# Brain_0_1_rv1.net
KiCad netlist of a schematic drawn in EAGLE
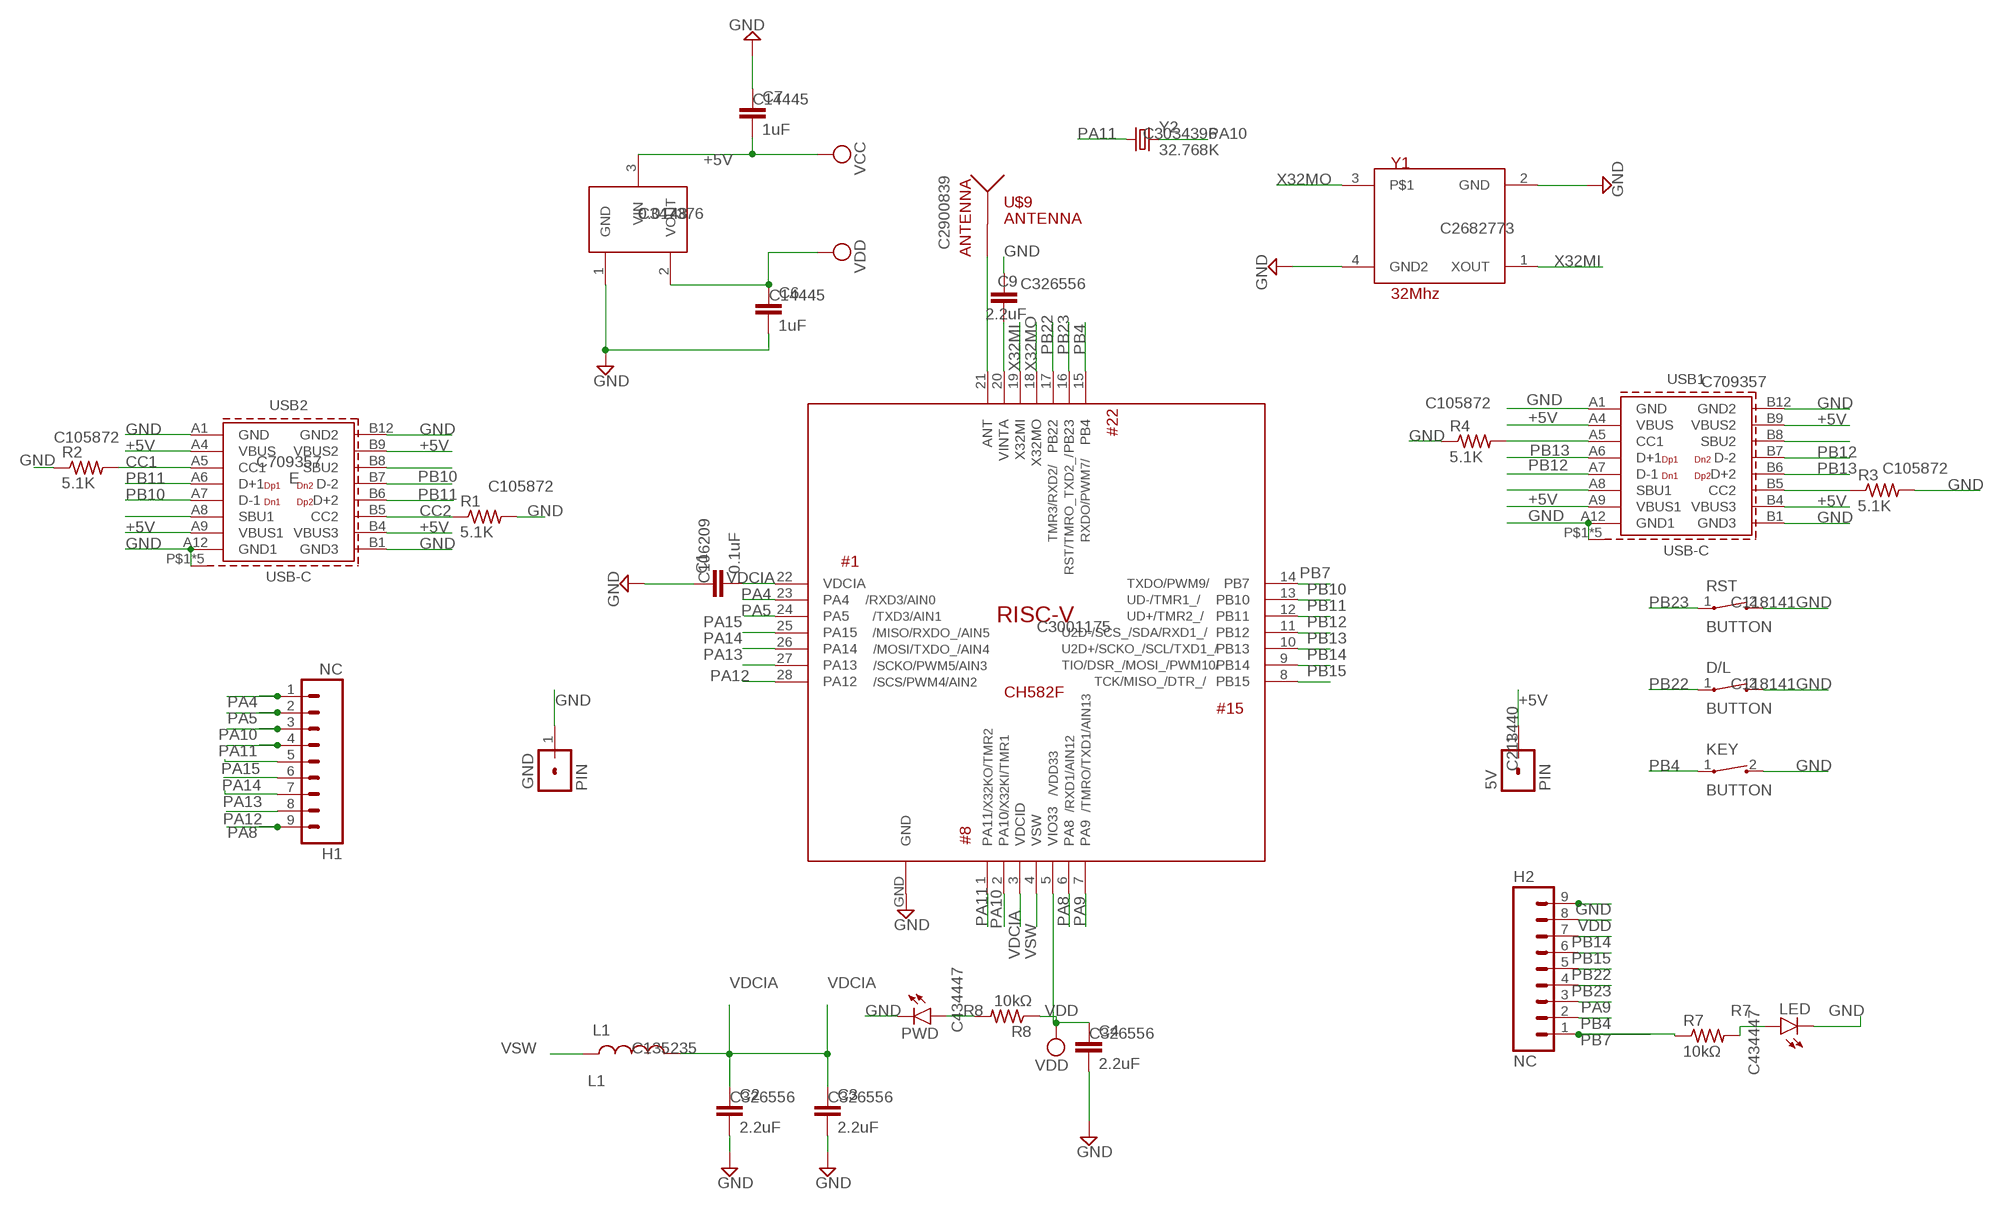
[diagram p0: schematic, sheet 1]

(export (version "E")
  (design (tool "Eeschema 10.0.6"))
  (components
    (comp (ref "5V")
      (value "PIN")
      (footprint "eagle-import:1X01")
      (fields (field (name "LCSC") "C213440"))
      (libsource (lib "eagle-import") (part "PIN"))
    )
    (comp (ref "C1")
      (value "0.1uF")
      (footprint "eagle-import:C1")
      (fields (field (name "LCSC") "C106209"))
      (libsource (lib "eagle-import") (part "C"))
    )
    (comp (ref "C2")
      (value "2.2uF")
      (footprint "eagle-import:C1")
      (fields (field (name "LCSC") "C326556"))
      (libsource (lib "eagle-import") (part "C"))
    )
    (comp (ref "C3")
      (value "2.2uF")
      (footprint "eagle-import:C1")
      (fields (field (name "LCSC") "C326556"))
      (libsource (lib "eagle-import") (part "C"))
    )
    (comp (ref "C4")
      (value "2.2uF")
      (footprint "eagle-import:C1")
      (fields (field (name "LCSC") "C326556"))
      (libsource (lib "eagle-import") (part "C"))
    )
    (comp (ref "C6")
      (value "1uF")
      (footprint "eagle-import:C1")
      (fields (field (name "LCSC") "C14445"))
      (libsource (lib "eagle-import") (part "C"))
    )
    (comp (ref "C7")
      (value "1uF")
      (footprint "eagle-import:C1")
      (fields (field (name "LCSC") "C14445"))
      (libsource (lib "eagle-import") (part "C"))
    )
    (comp (ref "C9")
      (value "2.2uF")
      (footprint "eagle-import:C1")
      (fields (field (name "LCSC") "C326556"))
      (libsource (lib "eagle-import") (part "C"))
    )
    (comp (ref "D/L")
      (value "BUTTON")
      (footprint "eagle-import:SOD8037X250N")
      (fields (field (name "LCSC") "C118141"))
      (libsource (lib "eagle-import") (part "BUTTON"))
    )
    (comp (ref "GND")
      (value "PIN")
      (footprint "eagle-import:1X01")
      (libsource (lib "eagle-import") (part "PIN"))
    )
    (comp (ref "H1")
      (value "NC")
      (footprint "eagle-import:61300911821")
      (libsource (lib "eagle-import") (part "H"))
    )
    (comp (ref "H2")
      (value "NC")
      (footprint "eagle-import:61300911821")
      (libsource (lib "eagle-import") (part "H"))
    )
    (comp (ref "KEY")
      (value "BUTTON")
      (footprint "eagle-import:SOD8037X250N")
      (libsource (lib "eagle-import") (part "BUTTON"))
    )
    (comp (ref "L1")
      (value "L1")
      (footprint "eagle-import:RESC3025X120N")
      (fields (field (name "LCSC") "C135235"))
      (libsource (lib "eagle-import") (part "L1"))
    )
    (comp (ref "LED")
      (value "LED")
      (footprint "eagle-import:CAPCP1005X40N")
      (fields (field (name "LCSC") "C434447"))
      (libsource (lib "eagle-import") (part "LED"))
    )
    (comp (ref "PWD")
      (value "LED")
      (footprint "eagle-import:CAPCP1005X40N")
      (fields (field (name "LCSC") "C434447"))
      (libsource (lib "eagle-import") (part "LED"))
    )
    (comp (ref "R1")
      (value "5.1K")
      (footprint "eagle-import:R0402")
      (fields (field (name "LCSC") "C105872"))
      (libsource (lib "eagle-import") (part "RR0402"))
    )
    (comp (ref "R2")
      (value "5.1K")
      (footprint "eagle-import:R0402")
      (fields (field (name "LCSC") "C105872"))
      (libsource (lib "eagle-import") (part "RR0402"))
    )
    (comp (ref "R3")
      (value "5.1K")
      (footprint "eagle-import:R0402")
      (fields (field (name "LCSC") "C105872"))
      (libsource (lib "eagle-import") (part "RR0402"))
    )
    (comp (ref "R4")
      (value "5.1K")
      (footprint "eagle-import:R0402")
      (fields (field (name "LCSC") "C105872"))
      (libsource (lib "eagle-import") (part "RR0402"))
    )
    (comp (ref "R7")
      (value "10kΩ")
      (footprint "eagle-import:R0402")
      (libsource (lib "eagle-import") (part "RR0402"))
    )
    (comp (ref "R8")
      (value "10kΩ")
      (footprint "eagle-import:R0402")
      (fields (field (name "LCSC_PART") "C25744"))
      (libsource (lib "eagle-import") (part "RR0402"))
    )
    (comp (ref "RST")
      (value "BUTTON")
      (footprint "eagle-import:SOD8037X250N")
      (fields (field (name "LCSC") "C118141"))
      (libsource (lib "eagle-import") (part "BUTTON"))
    )
    (comp (ref "U$8")
      (value "RISC-V")
      (footprint "eagle-import:QFN40P400X400X75-29T280N")
      (fields (field (name "LCSC") "C3001175"))
      (libsource (lib "eagle-import") (part "RISC-V"))
    )
    (comp (ref "U$9")
      (value "ANTENNA")
      (footprint "eagle-import:CAPCP3015X50N")
      (fields (field (name "LCSC") "C2900839"))
      (libsource (lib "eagle-import") (part "ANTENNA"))
    )
    (comp (ref "U1")
      (value "U1")
      (footprint "eagle-import:SOT95P240X90-3N")
      (fields (field (name "LCSC") "C347376") (field (name "PRICE-1000") "0.0148"))
      (libsource (lib "eagle-import") (part "U1"))
    )
    (comp (ref "USB1")
      (value "629722000214")
      (footprint "eagle-import:629722000214")
      (fields (field (name "LCSC") "C709357"))
      (libsource (lib "eagle-import") (part "J1"))
    )
    (comp (ref "USB2")
      (value "629722000214")
      (footprint "eagle-import:629722000214")
      (fields (field (name "LCSC") "C709357"))
      (libsource (lib "eagle-import") (part "J1"))
    )
    (comp (ref "Y1")
      (value "Y1YSX211SL")
      (footprint "eagle-import:OSCCC200X160X50N")
      (fields (field (name "LCSC") "C2682773"))
      (libsource (lib "eagle-import") (part "Y1YSX211SL"))
    )
    (comp (ref "Y2")
      (value "32.768K")
      (footprint "eagle-import:XTAL700X315X230N")
      (fields (field (name "LCSC") "C3034396"))
      (libsource (lib "eagle-import") (part "Y2"))
    )
  )
  (nets
    (net (code "1") (name "/CC1") (class "Default")
      (node (ref "R2") (pin "2") (pinfunction "2_2") (pintype "passive"))
      (node (ref "USB2") (pin "A5") (pinfunction "CC1_A5") (pintype "passive"))
    )
    (net (code "2") (name "/CC2") (class "Default")
      (node (ref "R1") (pin "1") (pinfunction "1_1") (pintype "passive"))
      (node (ref "USB2") (pin "B5") (pinfunction "CC2_B5") (pintype "passive"))
    )
    (net (code "3") (name "/PA4") (class "Default")
      (node (ref "H1") (pin "1") (pinfunction "1_1") (pintype "passive"))
      (node (ref "U$8") (pin "23") (pinfunction "PA4_23") (pintype "bidirectional"))
    )
    (net (code "4") (name "/PA5") (class "Default")
      (node (ref "H1") (pin "2") (pinfunction "2_2") (pintype "passive"))
      (node (ref "U$8") (pin "24") (pinfunction "PA5_24") (pintype "bidirectional"))
    )
    (net (code "5") (name "/PA8") (class "Default")
      (node (ref "H1") (pin "9") (pinfunction "9_9") (pintype "passive"))
      (node (ref "U$8") (pin "6") (pinfunction "PA8_6") (pintype "bidirectional"))
    )
    (net (code "6") (name "/PA9") (class "Default")
      (node (ref "H2") (pin "3") (pinfunction "3_3") (pintype "passive"))
      (node (ref "U$8") (pin "7") (pinfunction "PA9_7") (pintype "bidirectional"))
    )
    (net (code "7") (name "/PA10") (class "Default")
      (node (ref "H1") (pin "3") (pinfunction "3_3") (pintype "passive"))
      (node (ref "U$8") (pin "2") (pinfunction "PA10_2") (pintype "bidirectional"))
      (node (ref "Y2") (pin "2") (pinfunction "2_2") (pintype "passive"))
    )
    (net (code "8") (name "/PA11") (class "Default")
      (node (ref "H1") (pin "4") (pinfunction "4_4") (pintype "passive"))
      (node (ref "U$8") (pin "1") (pinfunction "PA11_1") (pintype "bidirectional"))
      (node (ref "Y2") (pin "1") (pinfunction "1_1") (pintype "passive"))
    )
    (net (code "9") (name "/PA12") (class "Default")
      (node (ref "H1") (pin "8") (pinfunction "8_8") (pintype "passive"))
      (node (ref "U$8") (pin "28") (pinfunction "PA12_28") (pintype "bidirectional"))
    )
    (net (code "10") (name "/PA13") (class "Default")
      (node (ref "H1") (pin "7") (pinfunction "7_7") (pintype "passive"))
      (node (ref "U$8") (pin "27") (pinfunction "PA13_27") (pintype "bidirectional"))
    )
    (net (code "11") (name "/PA14") (class "Default")
      (node (ref "H1") (pin "6") (pinfunction "6_6") (pintype "passive"))
      (node (ref "U$8") (pin "26") (pinfunction "PA14_26") (pintype "bidirectional"))
    )
    (net (code "12") (name "/PA15") (class "Default")
      (node (ref "H1") (pin "5") (pinfunction "5_5") (pintype "passive"))
      (node (ref "U$8") (pin "25") (pinfunction "PA15_25") (pintype "bidirectional"))
    )
    (net (code "13") (name "/PB4") (class "Default")
      (node (ref "H2") (pin "2") (pinfunction "2_2") (pintype "passive"))
      (node (ref "KEY") (pin "1") (pinfunction "1_1") (pintype "passive"))
      (node (ref "U$8") (pin "15") (pinfunction "PB4_15") (pintype "bidirectional"))
    )
    (net (code "14") (name "/PB7") (class "Default")
      (node (ref "H2") (pin "1") (pinfunction "1_1") (pintype "passive"))
      (node (ref "R7") (pin "1") (pinfunction "1_1") (pintype "passive"))
      (node (ref "U$8") (pin "14") (pinfunction "PB7_14") (pintype "bidirectional"))
    )
    (net (code "15") (name "/PB10") (class "Default")
      (node (ref "U$8") (pin "13") (pinfunction "PB10_13") (pintype "bidirectional"))
      (node (ref "USB2") (pin "A7") (pinfunction "D-1_A7") (pintype "passive"))
      (node (ref "USB2") (pin "B7") (pinfunction "D-2_B7") (pintype "passive"))
    )
    (net (code "16") (name "/PB11") (class "Default")
      (node (ref "U$8") (pin "12") (pinfunction "PB11_12") (pintype "bidirectional"))
      (node (ref "USB2") (pin "A6") (pinfunction "D+1_A6") (pintype "passive"))
      (node (ref "USB2") (pin "B6") (pinfunction "D+2_B6") (pintype "passive"))
    )
    (net (code "17") (name "/PB12") (class "Default")
      (node (ref "U$8") (pin "11") (pinfunction "PB12_11") (pintype "bidirectional"))
      (node (ref "USB1") (pin "A7") (pinfunction "D-1_A7") (pintype "passive"))
      (node (ref "USB1") (pin "B7") (pinfunction "D-2_B7") (pintype "passive"))
    )
    (net (code "18") (name "/PB13") (class "Default")
      (node (ref "U$8") (pin "10") (pinfunction "PB13_10") (pintype "bidirectional"))
      (node (ref "USB1") (pin "A6") (pinfunction "D+1_A6") (pintype "passive"))
      (node (ref "USB1") (pin "B6") (pinfunction "D+2_B6") (pintype "passive"))
    )
    (net (code "19") (name "/PB14") (class "Default")
      (node (ref "H2") (pin "7") (pinfunction "7_7") (pintype "passive"))
      (node (ref "U$8") (pin "9") (pinfunction "PB14_9") (pintype "bidirectional"))
    )
    (net (code "20") (name "/PB15") (class "Default")
      (node (ref "H2") (pin "6") (pinfunction "6_6") (pintype "passive"))
      (node (ref "U$8") (pin "8") (pinfunction "PB15_8") (pintype "bidirectional"))
    )
    (net (code "21") (name "/PB22") (class "Default")
      (node (ref "D/L") (pin "1") (pinfunction "1_1") (pintype "passive"))
      (node (ref "H2") (pin "5") (pinfunction "5_5") (pintype "passive"))
      (node (ref "U$8") (pin "17") (pinfunction "PB22_17") (pintype "bidirectional"))
    )
    (net (code "22") (name "/PB23") (class "Default")
      (node (ref "H2") (pin "4") (pinfunction "4_4") (pintype "passive"))
      (node (ref "RST") (pin "1") (pinfunction "1_1") (pintype "passive"))
      (node (ref "U$8") (pin "16") (pinfunction "PB23_16") (pintype "bidirectional"))
    )
    (net (code "23") (name "/R7") (class "Default")
      (node (ref "LED") (pin "A") (pinfunction "A_A") (pintype "passive"))
      (node (ref "R7") (pin "2") (pinfunction "2_2") (pintype "passive"))
    )
    (net (code "24") (name "/R8") (class "Default")
      (node (ref "PWD") (pin "A") (pinfunction "A_A") (pintype "passive"))
      (node (ref "R8") (pin "2") (pinfunction "2_2") (pintype "passive"))
    )
    (net (code "25") (name "/VDCIA") (class "Default")
      (node (ref "C1") (pin "2") (pinfunction "2_2") (pintype "passive"))
      (node (ref "C2") (pin "1") (pinfunction "1_1") (pintype "passive"))
      (node (ref "C3") (pin "1") (pinfunction "1_1") (pintype "passive"))
      (node (ref "L1") (pin "2") (pinfunction "2_2") (pintype "passive"))
      (node (ref "U$8") (pin "22") (pinfunction "VDCIA_22") (pintype "bidirectional"))
      (node (ref "U$8") (pin "3") (pinfunction "VDCID_3") (pintype "bidirectional"))
    )
    (net (code "26") (name "/VSW") (class "Default")
      (node (ref "L1") (pin "1") (pinfunction "1_1") (pintype "passive"))
      (node (ref "U$8") (pin "4") (pinfunction "VSW_4") (pintype "bidirectional"))
    )
    (net (code "27") (name "/X32MI") (class "Default")
      (node (ref "U$8") (pin "19") (pinfunction "X32MI_19") (pintype "bidirectional"))
      (node (ref "Y1") (pin "1") (pinfunction "XOUT_1") (pintype "bidirectional"))
    )
    (net (code "28") (name "/X32MO") (class "Default")
      (node (ref "U$8") (pin "18") (pinfunction "X32MO_18") (pintype "bidirectional"))
      (node (ref "Y1") (pin "3") (pinfunction "P$1_3") (pintype "bidirectional"))
    )
    (net (code "29") (name "GND") (class "Default")
      (node (ref "C1") (pin "1") (pinfunction "1_1") (pintype "passive"))
      (node (ref "C2") (pin "2") (pinfunction "2_2") (pintype "passive"))
      (node (ref "C3") (pin "2") (pinfunction "2_2") (pintype "passive"))
      (node (ref "C4") (pin "2") (pinfunction "2_2") (pintype "passive"))
      (node (ref "C6") (pin "2") (pinfunction "2_2") (pintype "passive"))
      (node (ref "C7") (pin "1") (pinfunction "1_1") (pintype "passive"))
      (node (ref "C9") (pin "1") (pinfunction "1_1") (pintype "passive"))
      (node (ref "D/L") (pin "2") (pinfunction "2_2") (pintype "passive"))
      (node (ref "GND") (pin "1") (pinfunction "1_1") (pintype "passive"))
      (node (ref "H2") (pin "9") (pinfunction "9_9") (pintype "passive"))
      (node (ref "KEY") (pin "2") (pinfunction "2_2") (pintype "passive"))
      (node (ref "LED") (pin "C") (pinfunction "C_C") (pintype "passive"))
      (node (ref "PWD") (pin "C") (pinfunction "C_C") (pintype "passive"))
      (node (ref "R1") (pin "2") (pinfunction "2_2") (pintype "passive"))
      (node (ref "R2") (pin "1") (pinfunction "1_1") (pintype "passive"))
      (node (ref "R3") (pin "2") (pinfunction "2_2") (pintype "passive"))
      (node (ref "R4") (pin "1") (pinfunction "1_1") (pintype "passive"))
      (node (ref "RST") (pin "2") (pinfunction "2_2") (pintype "passive"))
      (node (ref "U$8") (pin "GND") (pinfunction "GND_GND") (pintype "bidirectional"))
      (node (ref "U1") (pin "1") (pinfunction "GND_1") (pintype "bidirectional"))
      (node (ref "USB1") (pin "A1") (pinfunction "GND_A1") (pintype "passive"))
      (node (ref "USB1") (pin "A12") (pinfunction "GND1_A12") (pintype "passive"))
      (node (ref "USB1") (pin "B1") (pinfunction "GND3_B1") (pintype "passive"))
      (node (ref "USB1") (pin "B12") (pinfunction "GND2_B12") (pintype "passive"))
      (node (ref "USB1") (pin "P$1") (pinfunction "SHIELD_P$1") (pintype "passive"))
      (node (ref "USB1") (pin "S1") (pinfunction "SHIELD_S1") (pintype "passive"))
      (node (ref "USB1") (pin "S2") (pinfunction "SHIELD_S2") (pintype "passive"))
      (node (ref "USB1") (pin "S3") (pinfunction "SHIELD_S3") (pintype "passive"))
      (node (ref "USB1") (pin "S4") (pinfunction "SHIELD_S4") (pintype "passive"))
      (node (ref "USB2") (pin "A1") (pinfunction "GND_A1") (pintype "passive"))
      (node (ref "USB2") (pin "A12") (pinfunction "GND1_A12") (pintype "passive"))
      (node (ref "USB2") (pin "B1") (pinfunction "GND3_B1") (pintype "passive"))
      (node (ref "USB2") (pin "B12") (pinfunction "GND2_B12") (pintype "passive"))
      (node (ref "USB2") (pin "P$1") (pinfunction "SHIELD_P$1") (pintype "passive"))
      (node (ref "USB2") (pin "S1") (pinfunction "SHIELD_S1") (pintype "passive"))
      (node (ref "USB2") (pin "S2") (pinfunction "SHIELD_S2") (pintype "passive"))
      (node (ref "USB2") (pin "S3") (pinfunction "SHIELD_S3") (pintype "passive"))
      (node (ref "USB2") (pin "S4") (pinfunction "SHIELD_S4") (pintype "passive"))
      (node (ref "Y1") (pin "2") (pinfunction "GND_2") (pintype "bidirectional"))
      (node (ref "Y1") (pin "4") (pinfunction "GND2_4") (pintype "bidirectional"))
    )
    (net (code "30") (name "Net-(U$8-ANT)") (class "Default")
      (node (ref "U$8") (pin "21") (pinfunction "ANT_21") (pintype "bidirectional"))
      (node (ref "U$9") (pin "1") (pinfunction "P$1_1") (pintype "bidirectional"))
    )
    (net (code "31") (name "Net-(U$8-VINTA)") (class "Default")
      (node (ref "C9") (pin "2") (pinfunction "2_2") (pintype "passive"))
      (node (ref "U$8") (pin "20") (pinfunction "VINTA_20") (pintype "bidirectional"))
    )
    (net (code "32") (name "Net-(USB1-CC1)") (class "Default")
      (node (ref "R4") (pin "2") (pinfunction "2_2") (pintype "passive"))
      (node (ref "USB1") (pin "A5") (pinfunction "CC1_A5") (pintype "passive"))
    )
    (net (code "33") (name "Net-(USB1-CC2)") (class "Default")
      (node (ref "R3") (pin "1") (pinfunction "1_1") (pintype "passive"))
      (node (ref "USB1") (pin "B5") (pinfunction "CC2_B5") (pintype "passive"))
    )
    (net (code "34") (name "VCC") (class "Default")
      (node (ref "5V") (pin "1") (pinfunction "1_1") (pintype "passive"))
      (node (ref "C7") (pin "2") (pinfunction "2_2") (pintype "passive"))
      (node (ref "U1") (pin "3") (pinfunction "VIN_3") (pintype "input"))
      (node (ref "USB1") (pin "A4") (pinfunction "VBUS_A4") (pintype "passive"))
      (node (ref "USB1") (pin "A9") (pinfunction "VBUS1_A9") (pintype "passive"))
      (node (ref "USB1") (pin "B4") (pinfunction "VBUS3_B4") (pintype "passive"))
      (node (ref "USB1") (pin "B9") (pinfunction "VBUS2_B9") (pintype "passive"))
      (node (ref "USB2") (pin "A4") (pinfunction "VBUS_A4") (pintype "passive"))
      (node (ref "USB2") (pin "A9") (pinfunction "VBUS1_A9") (pintype "passive"))
      (node (ref "USB2") (pin "B4") (pinfunction "VBUS3_B4") (pintype "passive"))
      (node (ref "USB2") (pin "B9") (pinfunction "VBUS2_B9") (pintype "passive"))
    )
    (net (code "35") (name "VDD") (class "Default")
      (node (ref "C4") (pin "1") (pinfunction "1_1") (pintype "passive"))
      (node (ref "C6") (pin "1") (pinfunction "1_1") (pintype "passive"))
      (node (ref "H2") (pin "8") (pinfunction "8_8") (pintype "passive"))
      (node (ref "R8") (pin "1") (pinfunction "1_1") (pintype "passive"))
      (node (ref "U$8") (pin "5") (pinfunction "VIO33_5") (pintype "bidirectional"))
      (node (ref "U1") (pin "2") (pinfunction "VOUT_2") (pintype "output"))
    )
    (net (code "36") (name "unconnected-(U$9-P$2-Pad2)") (class "Default")
      (node (ref "U$9") (pin "2") (pinfunction "P$2_2") (pintype "bidirectional"))
    )
    (net (code "37") (name "unconnected-(USB1-SBU1-PadA8)") (class "Default")
      (node (ref "USB1") (pin "A8") (pinfunction "SBU1_A8") (pintype "passive"))
    )
    (net (code "38") (name "unconnected-(USB1-SBU2-PadB8)") (class "Default")
      (node (ref "USB1") (pin "B8") (pinfunction "SBU2_B8") (pintype "passive"))
    )
    (net (code "39") (name "unconnected-(USB2-SBU1-PadA8)") (class "Default")
      (node (ref "USB2") (pin "A8") (pinfunction "SBU1_A8") (pintype "passive"))
    )
    (net (code "40") (name "unconnected-(USB2-SBU2-PadB8)") (class "Default")
      (node (ref "USB2") (pin "B8") (pinfunction "SBU2_B8") (pintype "passive"))
    )
  )
)
